# calculator.net
KiCad netlist of a schematic drawn in EAGLE
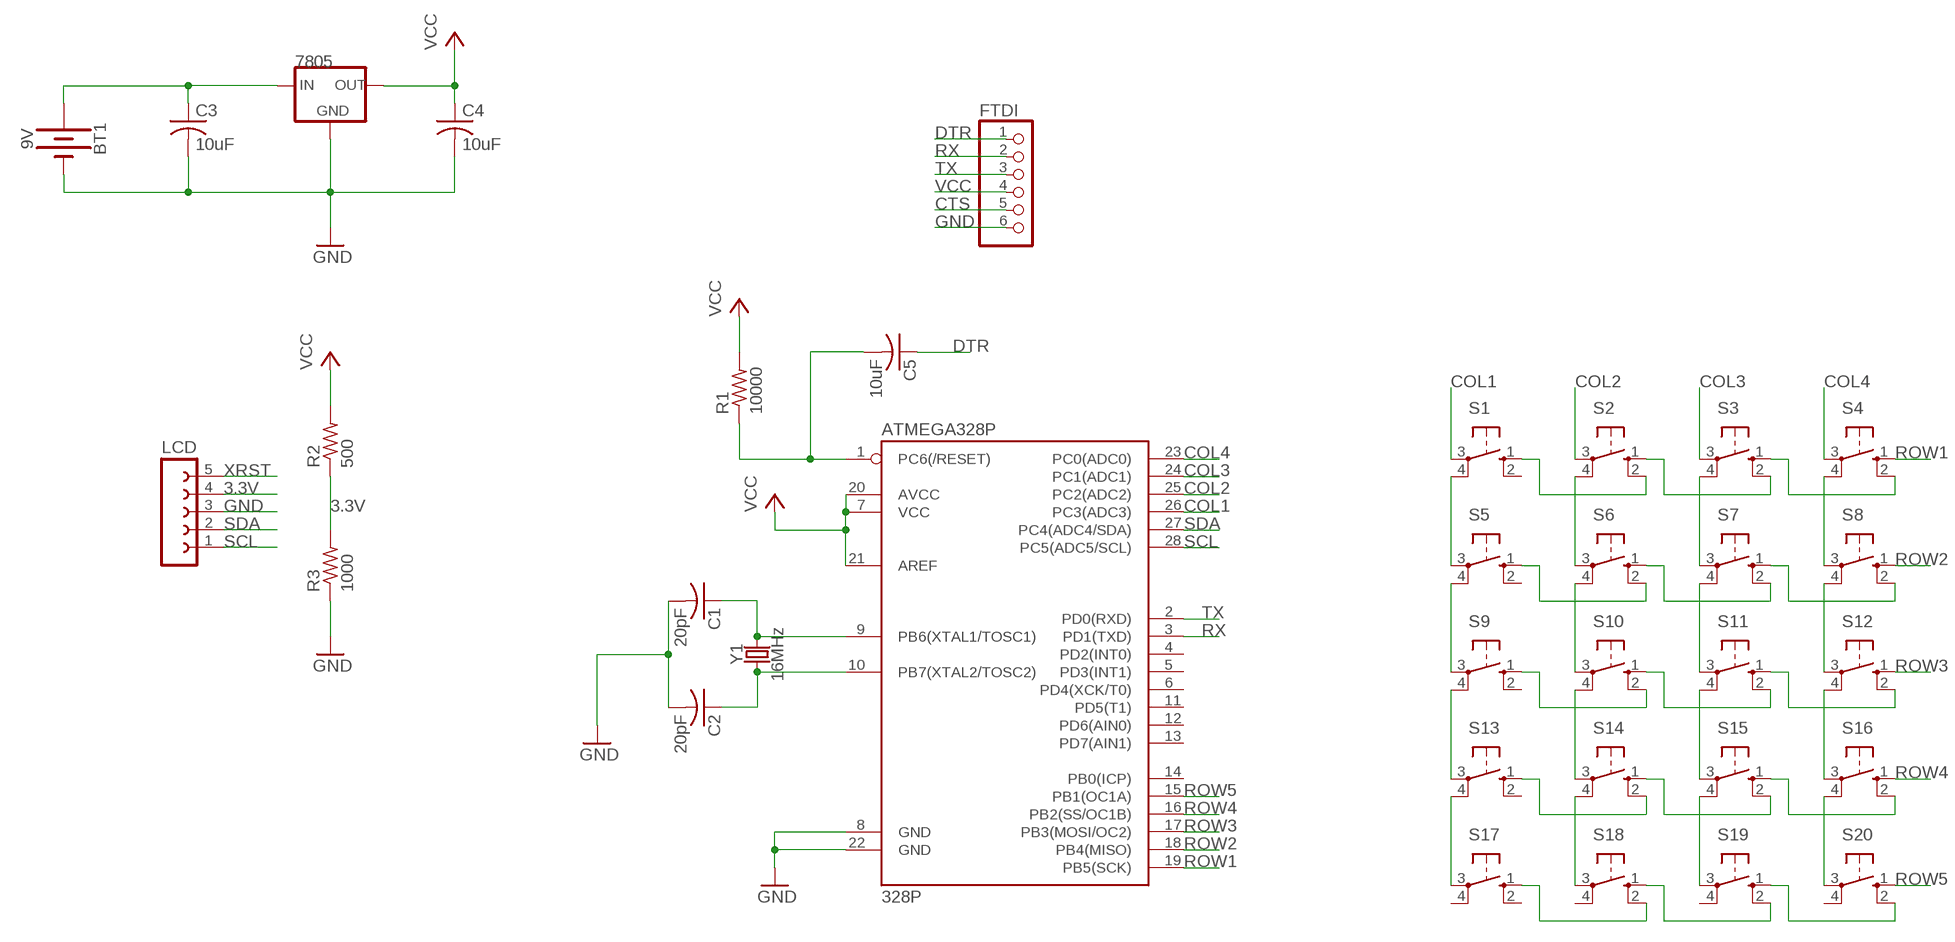
[diagram p0: schematic, sheet 1]

(export (version "E")
  (design (tool "Eeschema 10.0.6"))
  (components
    (comp (ref "7805")
      (value "78XXS")
      (footprint "eagle-import:78XXS")
      (libsource (lib "eagle-import") (part "78XXS"))
    )
    (comp (ref "ATMEGA328P")
      (value "328P")
      (footprint "eagle-import:DIP28")
      (libsource (lib "eagle-import") (part "ATMEGA328P_PDIP"))
    )
    (comp (ref "BT1")
      (value "9V")
      (footprint "eagle-import:BATTCON_9V")
      (libsource (lib "eagle-import") (part "BATTERY-9V"))
    )
    (comp (ref "C1")
      (value "20pF")
      (footprint "eagle-import:C025-024X044")
      (libsource (lib "eagle-import") (part "C-US025-024X044"))
    )
    (comp (ref "C2")
      (value "20pF")
      (footprint "eagle-import:C025-024X044")
      (libsource (lib "eagle-import") (part "C-US025-024X044"))
    )
    (comp (ref "C3")
      (value "10uF")
      (footprint "eagle-import:C025-024X044")
      (libsource (lib "eagle-import") (part "C-US025-024X044"))
    )
    (comp (ref "C4")
      (value "10uF")
      (footprint "eagle-import:C025-024X044")
      (libsource (lib "eagle-import") (part "C-US025-024X044"))
    )
    (comp (ref "C5")
      (value "10uF")
      (footprint "eagle-import:C025-024X044")
      (libsource (lib "eagle-import") (part "C-US025-024X044"))
    )
    (comp (ref "FTDI")
      (value "PINHD-1X6")
      (footprint "eagle-import:1X06")
      (libsource (lib "eagle-import") (part "PINHD-1X6"))
    )
    (comp (ref "LCD")
      (value "FE05-1")
      (footprint "eagle-import:FE05-1")
      (libsource (lib "eagle-import") (part "FE05-1"))
    )
    (comp (ref "R1")
      (value "10000")
      (footprint "eagle-import:0204_7")
      (libsource (lib "eagle-import") (part "R-US_0204/7"))
    )
    (comp (ref "R2")
      (value "500")
      (footprint "eagle-import:0204_7")
      (libsource (lib "eagle-import") (part "R-US_0204/7"))
    )
    (comp (ref "R3")
      (value "1000")
      (footprint "eagle-import:0204_7")
      (libsource (lib "eagle-import") (part "R-US_0204/7"))
    )
    (comp (ref "S1")
      (value "10-XX")
      (footprint "eagle-import:B3F-10XX")
      (fields (field (name "MPN") "B3F-1000"))
      (libsource (lib "eagle-import") (part "10-XX"))
    )
    (comp (ref "S2")
      (value "10-XX")
      (footprint "eagle-import:B3F-10XX")
      (fields (field (name "MPN") "B3F-1000"))
      (libsource (lib "eagle-import") (part "10-XX"))
    )
    (comp (ref "S3")
      (value "10-XX")
      (footprint "eagle-import:B3F-10XX")
      (fields (field (name "MPN") "B3F-1000"))
      (libsource (lib "eagle-import") (part "10-XX"))
    )
    (comp (ref "S4")
      (value "10-XX")
      (footprint "eagle-import:B3F-10XX")
      (fields (field (name "MPN") "B3F-1000"))
      (libsource (lib "eagle-import") (part "10-XX"))
    )
    (comp (ref "S5")
      (value "10-XX")
      (footprint "eagle-import:B3F-10XX")
      (fields (field (name "MPN") "B3F-1000"))
      (libsource (lib "eagle-import") (part "10-XX"))
    )
    (comp (ref "S6")
      (value "10-XX")
      (footprint "eagle-import:B3F-10XX")
      (fields (field (name "MPN") "B3F-1000"))
      (libsource (lib "eagle-import") (part "10-XX"))
    )
    (comp (ref "S7")
      (value "10-XX")
      (footprint "eagle-import:B3F-10XX")
      (fields (field (name "MPN") "B3F-1000"))
      (libsource (lib "eagle-import") (part "10-XX"))
    )
    (comp (ref "S8")
      (value "10-XX")
      (footprint "eagle-import:B3F-10XX")
      (fields (field (name "MPN") "B3F-1000"))
      (libsource (lib "eagle-import") (part "10-XX"))
    )
    (comp (ref "S9")
      (value "10-XX")
      (footprint "eagle-import:B3F-10XX")
      (fields (field (name "MPN") "B3F-1000"))
      (libsource (lib "eagle-import") (part "10-XX"))
    )
    (comp (ref "S10")
      (value "10-XX")
      (footprint "eagle-import:B3F-10XX")
      (fields (field (name "MPN") "B3F-1000"))
      (libsource (lib "eagle-import") (part "10-XX"))
    )
    (comp (ref "S11")
      (value "10-XX")
      (footprint "eagle-import:B3F-10XX")
      (fields (field (name "MPN") "B3F-1000"))
      (libsource (lib "eagle-import") (part "10-XX"))
    )
    (comp (ref "S12")
      (value "10-XX")
      (footprint "eagle-import:B3F-10XX")
      (fields (field (name "MPN") "B3F-1000"))
      (libsource (lib "eagle-import") (part "10-XX"))
    )
    (comp (ref "S13")
      (value "10-XX")
      (footprint "eagle-import:B3F-10XX")
      (fields (field (name "MPN") "B3F-1000"))
      (libsource (lib "eagle-import") (part "10-XX"))
    )
    (comp (ref "S14")
      (value "10-XX")
      (footprint "eagle-import:B3F-10XX")
      (fields (field (name "MPN") "B3F-1000"))
      (libsource (lib "eagle-import") (part "10-XX"))
    )
    (comp (ref "S15")
      (value "10-XX")
      (footprint "eagle-import:B3F-10XX")
      (fields (field (name "MPN") "B3F-1000"))
      (libsource (lib "eagle-import") (part "10-XX"))
    )
    (comp (ref "S16")
      (value "10-XX")
      (footprint "eagle-import:B3F-10XX")
      (fields (field (name "MPN") "B3F-1000"))
      (libsource (lib "eagle-import") (part "10-XX"))
    )
    (comp (ref "S17")
      (value "10-XX")
      (footprint "eagle-import:B3F-10XX")
      (fields (field (name "MPN") "B3F-1000"))
      (libsource (lib "eagle-import") (part "10-XX"))
    )
    (comp (ref "S18")
      (value "10-XX")
      (footprint "eagle-import:B3F-10XX")
      (fields (field (name "MPN") "B3F-1000"))
      (libsource (lib "eagle-import") (part "10-XX"))
    )
    (comp (ref "S19")
      (value "10-XX")
      (footprint "eagle-import:B3F-10XX")
      (fields (field (name "MPN") "B3F-1000"))
      (libsource (lib "eagle-import") (part "10-XX"))
    )
    (comp (ref "S20")
      (value "10-XX")
      (footprint "eagle-import:B3F-10XX")
      (fields (field (name "MPN") "B3F-1000"))
      (libsource (lib "eagle-import") (part "10-XX"))
    )
    (comp (ref "Y1")
      (value "16MHz")
      (footprint "eagle-import:HC49US")
      (libsource (lib "eagle-import") (part "CRYSTAL-16MHZPTH-HC49US"))
    )
  )
  (nets
    (net (code "1") (name "/3.3V") (class "Default")
      (node (ref "LCD") (pin "4") (pinfunction "4_4") (pintype "passive"))
      (node (ref "R2") (pin "1") (pinfunction "1_1") (pintype "passive"))
      (node (ref "R3") (pin "2") (pinfunction "2_2") (pintype "passive"))
    )
    (net (code "2") (name "/COL1") (class "Default")
      (node (ref "ATMEGA328P") (pin "26") (pinfunction "PC3(ADC3)_26") (pintype "bidirectional"))
      (node (ref "S1") (pin "3") (pinfunction "P_3") (pintype "passive"))
    )
    (net (code "3") (name "/COL2") (class "Default")
      (node (ref "ATMEGA328P") (pin "25") (pinfunction "PC2(ADC2)_25") (pintype "bidirectional"))
      (node (ref "S2") (pin "3") (pinfunction "P_3") (pintype "passive"))
    )
    (net (code "4") (name "/COL3") (class "Default")
      (node (ref "ATMEGA328P") (pin "24") (pinfunction "PC1(ADC1)_24") (pintype "bidirectional"))
      (node (ref "S3") (pin "3") (pinfunction "P_3") (pintype "passive"))
    )
    (net (code "5") (name "/COL4") (class "Default")
      (node (ref "ATMEGA328P") (pin "23") (pinfunction "PC0(ADC0)_23") (pintype "bidirectional"))
      (node (ref "S4") (pin "3") (pinfunction "P_3") (pintype "passive"))
    )
    (net (code "6") (name "/CTS") (class "Default")
      (node (ref "FTDI") (pin "5") (pinfunction "5_5") (pintype "passive"))
    )
    (net (code "7") (name "/DTR") (class "Default")
      (node (ref "C5") (pin "1") (pinfunction "1_1") (pintype "passive"))
      (node (ref "FTDI") (pin "1") (pinfunction "1_1") (pintype "passive"))
    )
    (net (code "8") (name "/ROW1") (class "Default")
      (node (ref "ATMEGA328P") (pin "19") (pinfunction "PB5(SCK)_19") (pintype "bidirectional"))
      (node (ref "S4") (pin "1") (pinfunction "S_1") (pintype "passive"))
    )
    (net (code "9") (name "/ROW2") (class "Default")
      (node (ref "ATMEGA328P") (pin "18") (pinfunction "PB4(MISO)_18") (pintype "bidirectional"))
      (node (ref "S8") (pin "1") (pinfunction "S_1") (pintype "passive"))
    )
    (net (code "10") (name "/ROW3") (class "Default")
      (node (ref "ATMEGA328P") (pin "17") (pinfunction "PB3(MOSI/OC2)_17") (pintype "bidirectional"))
      (node (ref "S12") (pin "1") (pinfunction "S_1") (pintype "passive"))
    )
    (net (code "11") (name "/ROW4") (class "Default")
      (node (ref "ATMEGA328P") (pin "16") (pinfunction "PB2(SS/OC1B)_16") (pintype "bidirectional"))
      (node (ref "S16") (pin "1") (pinfunction "S_1") (pintype "passive"))
    )
    (net (code "12") (name "/ROW5") (class "Default")
      (node (ref "ATMEGA328P") (pin "15") (pinfunction "PB1(OC1A)_15") (pintype "bidirectional"))
      (node (ref "S20") (pin "1") (pinfunction "S_1") (pintype "passive"))
    )
    (net (code "13") (name "/RX") (class "Default")
      (node (ref "ATMEGA328P") (pin "3") (pinfunction "PD1(TXD)_3") (pintype "bidirectional"))
      (node (ref "FTDI") (pin "2") (pinfunction "2_2") (pintype "passive"))
    )
    (net (code "14") (name "/SCL") (class "Default")
      (node (ref "ATMEGA328P") (pin "28") (pinfunction "PC5(ADC5/SCL)_28") (pintype "bidirectional"))
      (node (ref "LCD") (pin "1") (pinfunction "1_1") (pintype "passive"))
    )
    (net (code "15") (name "/SDA") (class "Default")
      (node (ref "ATMEGA328P") (pin "27") (pinfunction "PC4(ADC4/SDA)_27") (pintype "bidirectional"))
      (node (ref "LCD") (pin "2") (pinfunction "2_2") (pintype "passive"))
    )
    (net (code "16") (name "/TX") (class "Default")
      (node (ref "ATMEGA328P") (pin "2") (pinfunction "PD0(RXD)_2") (pintype "bidirectional"))
      (node (ref "FTDI") (pin "3") (pinfunction "3_3") (pintype "passive"))
    )
    (net (code "17") (name "/XRST") (class "Default")
      (node (ref "LCD") (pin "5") (pinfunction "5_5") (pintype "passive"))
    )
    (net (code "18") (name "GND") (class "Default")
      (node (ref "7805") (pin "GND") (pinfunction "GND_GND") (pintype "input"))
      (node (ref "ATMEGA328P") (pin "22") (pinfunction "GND_22") (pintype "bidirectional"))
      (node (ref "ATMEGA328P") (pin "8") (pinfunction "GND_8") (pintype "bidirectional"))
      (node (ref "BT1") (pin "-") (pinfunction "-_-") (pintype "power_in"))
      (node (ref "C1") (pin "2") (pinfunction "2_2") (pintype "passive"))
      (node (ref "C2") (pin "2") (pinfunction "2_2") (pintype "passive"))
      (node (ref "C3") (pin "2") (pinfunction "2_2") (pintype "passive"))
      (node (ref "C4") (pin "2") (pinfunction "2_2") (pintype "passive"))
      (node (ref "FTDI") (pin "6") (pinfunction "6_6") (pintype "passive"))
      (node (ref "LCD") (pin "3") (pinfunction "3_3") (pintype "passive"))
      (node (ref "R3") (pin "1") (pinfunction "1_1") (pintype "passive"))
    )
    (net (code "19") (name "Net-(7805-PadIN)") (class "Default")
      (node (ref "7805") (pin "IN") (pinfunction "IN_IN") (pintype "input"))
      (node (ref "BT1") (pin "+") (pinfunction "+_+") (pintype "power_in"))
      (node (ref "C3") (pin "1") (pinfunction "1_1") (pintype "passive"))
    )
    (net (code "20") (name "Net-(ATMEGA328P-PB6(XTAL1{slash}TOSC1))") (class "Default")
      (node (ref "ATMEGA328P") (pin "9") (pinfunction "PB6(XTAL1/TOSC1)_9") (pintype "bidirectional"))
      (node (ref "C1") (pin "1") (pinfunction "1_1") (pintype "passive"))
      (node (ref "Y1") (pin "2") (pinfunction "2_2") (pintype "passive"))
    )
    (net (code "21") (name "Net-(ATMEGA328P-PB7(XTAL2{slash}TOSC2))") (class "Default")
      (node (ref "ATMEGA328P") (pin "10") (pinfunction "PB7(XTAL2/TOSC2)_10") (pintype "bidirectional"))
      (node (ref "C2") (pin "1") (pinfunction "1_1") (pintype "passive"))
      (node (ref "Y1") (pin "1") (pinfunction "1_1") (pintype "passive"))
    )
    (net (code "22") (name "Net-(ATMEGA328P-PC6({slash}RESET))") (class "Default")
      (node (ref "ATMEGA328P") (pin "1") (pinfunction "PC6(/RESET)_1") (pintype "bidirectional"))
      (node (ref "C5") (pin "2") (pinfunction "2_2") (pintype "passive"))
      (node (ref "R1") (pin "1") (pinfunction "1_1") (pintype "passive"))
    )
    (net (code "23") (name "Net-(S1-P1)") (class "Default")
      (node (ref "S1") (pin "4") (pinfunction "P1_4") (pintype "passive"))
      (node (ref "S5") (pin "3") (pinfunction "P_3") (pintype "passive"))
    )
    (net (code "24") (name "Net-(S1-S)") (class "Default")
      (node (ref "S1") (pin "1") (pinfunction "S_1") (pintype "passive"))
      (node (ref "S2") (pin "2") (pinfunction "S1_2") (pintype "passive"))
    )
    (net (code "25") (name "Net-(S2-P1)") (class "Default")
      (node (ref "S2") (pin "4") (pinfunction "P1_4") (pintype "passive"))
      (node (ref "S6") (pin "3") (pinfunction "P_3") (pintype "passive"))
    )
    (net (code "26") (name "Net-(S2-S)") (class "Default")
      (node (ref "S2") (pin "1") (pinfunction "S_1") (pintype "passive"))
      (node (ref "S3") (pin "2") (pinfunction "S1_2") (pintype "passive"))
    )
    (net (code "27") (name "Net-(S3-P1)") (class "Default")
      (node (ref "S3") (pin "4") (pinfunction "P1_4") (pintype "passive"))
      (node (ref "S7") (pin "3") (pinfunction "P_3") (pintype "passive"))
    )
    (net (code "28") (name "Net-(S3-S)") (class "Default")
      (node (ref "S3") (pin "1") (pinfunction "S_1") (pintype "passive"))
      (node (ref "S4") (pin "2") (pinfunction "S1_2") (pintype "passive"))
    )
    (net (code "29") (name "Net-(S4-P1)") (class "Default")
      (node (ref "S4") (pin "4") (pinfunction "P1_4") (pintype "passive"))
      (node (ref "S8") (pin "3") (pinfunction "P_3") (pintype "passive"))
    )
    (net (code "30") (name "Net-(S5-P1)") (class "Default")
      (node (ref "S5") (pin "4") (pinfunction "P1_4") (pintype "passive"))
      (node (ref "S9") (pin "3") (pinfunction "P_3") (pintype "passive"))
    )
    (net (code "31") (name "Net-(S5-S)") (class "Default")
      (node (ref "S5") (pin "1") (pinfunction "S_1") (pintype "passive"))
      (node (ref "S6") (pin "2") (pinfunction "S1_2") (pintype "passive"))
    )
    (net (code "32") (name "Net-(S6-S)") (class "Default")
      (node (ref "S6") (pin "1") (pinfunction "S_1") (pintype "passive"))
      (node (ref "S7") (pin "2") (pinfunction "S1_2") (pintype "passive"))
    )
    (net (code "33") (name "Net-(S7-S)") (class "Default")
      (node (ref "S7") (pin "1") (pinfunction "S_1") (pintype "passive"))
      (node (ref "S8") (pin "2") (pinfunction "S1_2") (pintype "passive"))
    )
    (net (code "34") (name "Net-(S10-P)") (class "Default")
      (node (ref "S10") (pin "3") (pinfunction "P_3") (pintype "passive"))
      (node (ref "S6") (pin "4") (pinfunction "P1_4") (pintype "passive"))
    )
    (net (code "35") (name "Net-(S10-P1)") (class "Default")
      (node (ref "S10") (pin "4") (pinfunction "P1_4") (pintype "passive"))
      (node (ref "S14") (pin "3") (pinfunction "P_3") (pintype "passive"))
    )
    (net (code "36") (name "Net-(S10-S)") (class "Default")
      (node (ref "S10") (pin "1") (pinfunction "S_1") (pintype "passive"))
      (node (ref "S11") (pin "2") (pinfunction "S1_2") (pintype "passive"))
    )
    (net (code "37") (name "Net-(S10-S1)") (class "Default")
      (node (ref "S10") (pin "2") (pinfunction "S1_2") (pintype "passive"))
      (node (ref "S9") (pin "1") (pinfunction "S_1") (pintype "passive"))
    )
    (net (code "38") (name "Net-(S11-P)") (class "Default")
      (node (ref "S11") (pin "3") (pinfunction "P_3") (pintype "passive"))
      (node (ref "S7") (pin "4") (pinfunction "P1_4") (pintype "passive"))
    )
    (net (code "39") (name "Net-(S11-P1)") (class "Default")
      (node (ref "S11") (pin "4") (pinfunction "P1_4") (pintype "passive"))
      (node (ref "S15") (pin "3") (pinfunction "P_3") (pintype "passive"))
    )
    (net (code "40") (name "Net-(S11-S)") (class "Default")
      (node (ref "S11") (pin "1") (pinfunction "S_1") (pintype "passive"))
      (node (ref "S12") (pin "2") (pinfunction "S1_2") (pintype "passive"))
    )
    (net (code "41") (name "Net-(S12-P)") (class "Default")
      (node (ref "S12") (pin "3") (pinfunction "P_3") (pintype "passive"))
      (node (ref "S8") (pin "4") (pinfunction "P1_4") (pintype "passive"))
    )
    (net (code "42") (name "Net-(S12-P1)") (class "Default")
      (node (ref "S12") (pin "4") (pinfunction "P1_4") (pintype "passive"))
      (node (ref "S16") (pin "3") (pinfunction "P_3") (pintype "passive"))
    )
    (net (code "43") (name "Net-(S13-P)") (class "Default")
      (node (ref "S13") (pin "3") (pinfunction "P_3") (pintype "passive"))
      (node (ref "S9") (pin "4") (pinfunction "P1_4") (pintype "passive"))
    )
    (net (code "44") (name "Net-(S13-P1)") (class "Default")
      (node (ref "S13") (pin "4") (pinfunction "P1_4") (pintype "passive"))
      (node (ref "S17") (pin "3") (pinfunction "P_3") (pintype "passive"))
    )
    (net (code "45") (name "Net-(S13-S)") (class "Default")
      (node (ref "S13") (pin "1") (pinfunction "S_1") (pintype "passive"))
      (node (ref "S14") (pin "2") (pinfunction "S1_2") (pintype "passive"))
    )
    (net (code "46") (name "Net-(S14-P1)") (class "Default")
      (node (ref "S14") (pin "4") (pinfunction "P1_4") (pintype "passive"))
      (node (ref "S18") (pin "3") (pinfunction "P_3") (pintype "passive"))
    )
    (net (code "47") (name "Net-(S14-S)") (class "Default")
      (node (ref "S14") (pin "1") (pinfunction "S_1") (pintype "passive"))
      (node (ref "S15") (pin "2") (pinfunction "S1_2") (pintype "passive"))
    )
    (net (code "48") (name "Net-(S15-P1)") (class "Default")
      (node (ref "S15") (pin "4") (pinfunction "P1_4") (pintype "passive"))
      (node (ref "S19") (pin "3") (pinfunction "P_3") (pintype "passive"))
    )
    (net (code "49") (name "Net-(S15-S)") (class "Default")
      (node (ref "S15") (pin "1") (pinfunction "S_1") (pintype "passive"))
      (node (ref "S16") (pin "2") (pinfunction "S1_2") (pintype "passive"))
    )
    (net (code "50") (name "Net-(S16-P1)") (class "Default")
      (node (ref "S16") (pin "4") (pinfunction "P1_4") (pintype "passive"))
      (node (ref "S20") (pin "3") (pinfunction "P_3") (pintype "passive"))
    )
    (net (code "51") (name "Net-(S17-S)") (class "Default")
      (node (ref "S17") (pin "1") (pinfunction "S_1") (pintype "passive"))
      (node (ref "S18") (pin "2") (pinfunction "S1_2") (pintype "passive"))
    )
    (net (code "52") (name "Net-(S18-S)") (class "Default")
      (node (ref "S18") (pin "1") (pinfunction "S_1") (pintype "passive"))
      (node (ref "S19") (pin "2") (pinfunction "S1_2") (pintype "passive"))
    )
    (net (code "53") (name "Net-(S19-S)") (class "Default")
      (node (ref "S19") (pin "1") (pinfunction "S_1") (pintype "passive"))
      (node (ref "S20") (pin "2") (pinfunction "S1_2") (pintype "passive"))
    )
    (net (code "54") (name "VCC") (class "Default")
      (node (ref "7805") (pin "OUT") (pinfunction "OUT_OUT") (pintype "passive"))
      (node (ref "ATMEGA328P") (pin "20") (pinfunction "AVCC_20") (pintype "bidirectional"))
      (node (ref "ATMEGA328P") (pin "21") (pinfunction "AREF_21") (pintype "bidirectional"))
      (node (ref "ATMEGA328P") (pin "7") (pinfunction "VCC_7") (pintype "bidirectional"))
      (node (ref "C4") (pin "1") (pinfunction "1_1") (pintype "passive"))
      (node (ref "FTDI") (pin "4") (pinfunction "4_4") (pintype "passive"))
      (node (ref "R1") (pin "2") (pinfunction "2_2") (pintype "passive"))
      (node (ref "R2") (pin "2") (pinfunction "2_2") (pintype "passive"))
    )
    (net (code "55") (name "unconnected-(ATMEGA328P-PB0(ICP)-Pad14)") (class "Default")
      (node (ref "ATMEGA328P") (pin "14") (pinfunction "PB0(ICP)_14") (pintype "bidirectional"))
    )
    (net (code "56") (name "unconnected-(ATMEGA328P-PD2(INT0)-Pad4)") (class "Default")
      (node (ref "ATMEGA328P") (pin "4") (pinfunction "PD2(INT0)_4") (pintype "bidirectional"))
    )
    (net (code "57") (name "unconnected-(ATMEGA328P-PD3(INT1)-Pad5)") (class "Default")
      (node (ref "ATMEGA328P") (pin "5") (pinfunction "PD3(INT1)_5") (pintype "bidirectional"))
    )
    (net (code "58") (name "unconnected-(ATMEGA328P-PD4(XCK{slash}T0)-Pad6)") (class "Default")
      (node (ref "ATMEGA328P") (pin "6") (pinfunction "PD4(XCK/T0)_6") (pintype "bidirectional"))
    )
    (net (code "59") (name "unconnected-(ATMEGA328P-PD5(T1)-Pad11)") (class "Default")
      (node (ref "ATMEGA328P") (pin "11") (pinfunction "PD5(T1)_11") (pintype "bidirectional"))
    )
    (net (code "60") (name "unconnected-(ATMEGA328P-PD6(AIN0)-Pad12)") (class "Default")
      (node (ref "ATMEGA328P") (pin "12") (pinfunction "PD6(AIN0)_12") (pintype "bidirectional"))
    )
    (net (code "61") (name "unconnected-(ATMEGA328P-PD7(AIN1)-Pad13)") (class "Default")
      (node (ref "ATMEGA328P") (pin "13") (pinfunction "PD7(AIN1)_13") (pintype "bidirectional"))
    )
    (net (code "62") (name "unconnected-(S1-S1-Pad2)") (class "Default")
      (node (ref "S1") (pin "2") (pinfunction "S1_2") (pintype "passive"))
    )
    (net (code "63") (name "unconnected-(S5-S1-Pad2)") (class "Default")
      (node (ref "S5") (pin "2") (pinfunction "S1_2") (pintype "passive"))
    )
    (net (code "64") (name "unconnected-(S9-S1-Pad2)") (class "Default")
      (node (ref "S9") (pin "2") (pinfunction "S1_2") (pintype "passive"))
    )
    (net (code "65") (name "unconnected-(S13-S1-Pad2)") (class "Default")
      (node (ref "S13") (pin "2") (pinfunction "S1_2") (pintype "passive"))
    )
    (net (code "66") (name "unconnected-(S17-P1-Pad4)") (class "Default")
      (node (ref "S17") (pin "4") (pinfunction "P1_4") (pintype "passive"))
    )
    (net (code "67") (name "unconnected-(S17-S1-Pad2)") (class "Default")
      (node (ref "S17") (pin "2") (pinfunction "S1_2") (pintype "passive"))
    )
    (net (code "68") (name "unconnected-(S18-P1-Pad4)") (class "Default")
      (node (ref "S18") (pin "4") (pinfunction "P1_4") (pintype "passive"))
    )
    (net (code "69") (name "unconnected-(S19-P1-Pad4)") (class "Default")
      (node (ref "S19") (pin "4") (pinfunction "P1_4") (pintype "passive"))
    )
    (net (code "70") (name "unconnected-(S20-P1-Pad4)") (class "Default")
      (node (ref "S20") (pin "4") (pinfunction "P1_4") (pintype "passive"))
    )
  )
)
